# solar_rpof.net
KiCad netlist of a schematic drawn in EAGLE
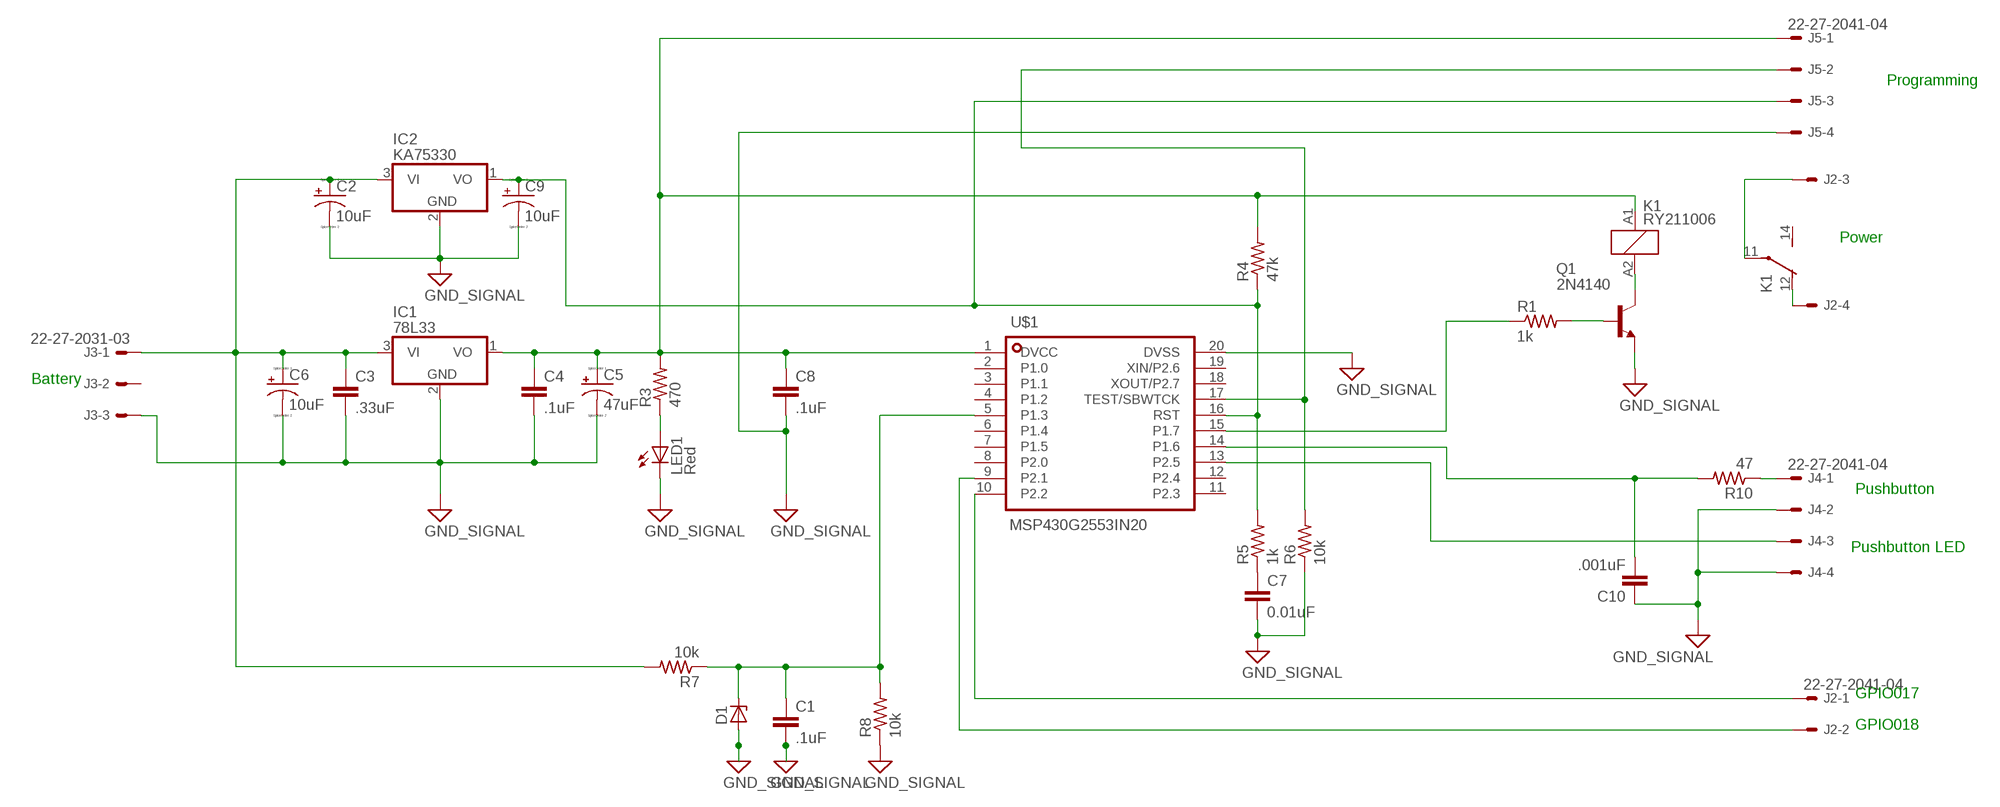
[diagram p0: schematic, sheet 1]

(export (version "E")
  (design (tool "Eeschema 10.0.6"))
  (components
    (comp (ref "C1")
      (value ".1uF")
      (footprint "eagle-import:C2.5-2")
      (libsource (lib "eagle-import") (part "C2.5/2"))
    )
    (comp (ref "C2")
      (value "10uF")
      (footprint "eagle-import:B45181A")
      (libsource (lib "eagle-import") (part "CPOL-USB45181A"))
    )
    (comp (ref "C3")
      (value ".33uF")
      (footprint "eagle-import:C2.5-2")
      (libsource (lib "eagle-import") (part "C2.5/2"))
    )
    (comp (ref "C4")
      (value ".1uF")
      (footprint "eagle-import:C2.5-2")
      (libsource (lib "eagle-import") (part "C2.5/2"))
    )
    (comp (ref "C5")
      (value "47uF")
      (footprint "eagle-import:B45181A")
      (libsource (lib "eagle-import") (part "CPOL-USB45181A"))
    )
    (comp (ref "C6")
      (value "10uF")
      (footprint "eagle-import:B45181A")
      (libsource (lib "eagle-import") (part "CPOL-USB45181A"))
    )
    (comp (ref "C7")
      (value "0.01uF")
      (footprint "eagle-import:C2.5-2")
      (libsource (lib "eagle-import") (part "C2.5/2"))
    )
    (comp (ref "C8")
      (value ".1uF")
      (footprint "eagle-import:C2.5-2")
      (libsource (lib "eagle-import") (part "C2.5/2"))
    )
    (comp (ref "C9")
      (value "10uF")
      (footprint "eagle-import:B45181A")
      (libsource (lib "eagle-import") (part "CPOL-USB45181A"))
    )
    (comp (ref "C10")
      (value ".001uF")
      (footprint "eagle-import:C2.5-2")
      (libsource (lib "eagle-import") (part "C2.5/2"))
    )
    (comp (ref "D1")
      (value "ZENER-DIODEDO34-7")
      (footprint "eagle-import:DO34Z7")
      (libsource (lib "eagle-import") (part "ZENER-DIODEDO34-7"))
    )
    (comp (ref "IC1")
      (value "78L33")
      (footprint "eagle-import:TO92")
      (libsource (lib "eagle-import") (part "78ZL05"))
    )
    (comp (ref "IC2")
      (value "KA75330")
      (footprint "eagle-import:TO92")
      (libsource (lib "eagle-import") (part "78ZL05"))
    )
    (comp (ref "J2")
      (value "22-27-2041-04")
      (footprint "eagle-import:6410-04")
      (libsource (lib "eagle-import") (part "22-?-0427-2041"))
    )
    (comp (ref "J3")
      (value "22-27-2031-03")
      (footprint "eagle-import:6410-03")
      (libsource (lib "eagle-import") (part "22-?-0327-2031"))
    )
    (comp (ref "J4")
      (value "22-27-2041-04")
      (footprint "eagle-import:6410-04")
      (libsource (lib "eagle-import") (part "22-?-0427-2041"))
    )
    (comp (ref "J5")
      (value "22-27-2041-04")
      (footprint "eagle-import:6410-04")
      (libsource (lib "eagle-import") (part "22-?-0427-2041"))
    )
    (comp (ref "K1")
      (value "RY211006")
      (footprint "eagle-import:RY-II")
      (fields (field (name "MF") "TYCO ELECTRONICS") (field (name "MPN") "4-1393224-3"))
      (libsource (lib "eagle-import") (part "RY?121006"))
    )
    (comp (ref "LED1")
      (value "Red")
      (footprint "eagle-import:LED3MM")
      (libsource (lib "eagle-import") (part "LED3MM"))
    )
    (comp (ref "Q1")
      (value "2N4140")
      (footprint "eagle-import:TO18")
      (libsource (lib "eagle-import") (part "2N4104"))
    )
    (comp (ref "R1")
      (value "1k")
      (footprint "eagle-import:0204_7")
      (libsource (lib "eagle-import") (part "R-US_0204/7"))
    )
    (comp (ref "R3")
      (value "470")
      (footprint "eagle-import:0204_7")
      (libsource (lib "eagle-import") (part "R-US_0204/7"))
    )
    (comp (ref "R4")
      (value "47k")
      (footprint "eagle-import:0204_7")
      (libsource (lib "eagle-import") (part "R-US_0204/7"))
    )
    (comp (ref "R5")
      (value "1k")
      (footprint "eagle-import:0204_7")
      (libsource (lib "eagle-import") (part "R-US_0204/7"))
    )
    (comp (ref "R6")
      (value "10k")
      (footprint "eagle-import:0204_7")
      (libsource (lib "eagle-import") (part "R-US_0204/7"))
    )
    (comp (ref "R7")
      (value "10k")
      (footprint "eagle-import:0204_7")
      (libsource (lib "eagle-import") (part "R-US_0204/7"))
    )
    (comp (ref "R8")
      (value "10k")
      (footprint "eagle-import:0204_7")
      (libsource (lib "eagle-import") (part "R-US_0204/7"))
    )
    (comp (ref "R10")
      (value "47")
      (footprint "eagle-import:0204_7")
      (libsource (lib "eagle-import") (part "R-US_0204/7"))
    )
    (comp (ref "U$1")
      (value "MSP430G2553IN20")
      (footprint "eagle-import:DIP20")
      (libsource (lib "eagle-import") (part "MSP430G2553IN20"))
    )
  )
  (nets
    (net (code "1") (name "GND_SIGNAL") (class "Default")
      (node (ref "C1") (pin "2") (pinfunction "2_2") (pintype "passive"))
      (node (ref "C10") (pin "1") (pinfunction "1_1") (pintype "passive"))
      (node (ref "C2") (pin "-") (pinfunction "-_-") (pintype "passive"))
      (node (ref "C3") (pin "2") (pinfunction "2_2") (pintype "passive"))
      (node (ref "C4") (pin "2") (pinfunction "2_2") (pintype "passive"))
      (node (ref "C5") (pin "-") (pinfunction "-_-") (pintype "passive"))
      (node (ref "C6") (pin "-") (pinfunction "-_-") (pintype "passive"))
      (node (ref "C7") (pin "2") (pinfunction "2_2") (pintype "passive"))
      (node (ref "C8") (pin "2") (pinfunction "2_2") (pintype "passive"))
      (node (ref "C9") (pin "-") (pinfunction "-_-") (pintype "passive"))
      (node (ref "D1") (pin "A") (pinfunction "A_A") (pintype "passive"))
      (node (ref "IC1") (pin "2") (pinfunction "GND_2") (pintype "passive"))
      (node (ref "IC2") (pin "2") (pinfunction "GND_2") (pintype "passive"))
      (node (ref "J3") (pin "3") (pinfunction "S_3") (pintype "passive"))
      (node (ref "J4") (pin "2") (pinfunction "S_2") (pintype "passive"))
      (node (ref "J4") (pin "4") (pinfunction "S_4") (pintype "passive"))
      (node (ref "J5") (pin "4") (pinfunction "S_4") (pintype "passive"))
      (node (ref "LED1") (pin "K") (pinfunction "C_K") (pintype "passive"))
      (node (ref "Q1") (pin "1") (pinfunction "E_1") (pintype "passive"))
      (node (ref "R6") (pin "1") (pinfunction "1_1") (pintype "passive"))
      (node (ref "R8") (pin "1") (pinfunction "1_1") (pintype "passive"))
      (node (ref "U$1") (pin "20") (pinfunction "DVSS_20") (pintype "power_in"))
    )
    (net (code "2") (name "Net-(C7-Pad1)") (class "Default")
      (node (ref "C7") (pin "1") (pinfunction "1_1") (pintype "passive"))
      (node (ref "R5") (pin "1") (pinfunction "1_1") (pintype "passive"))
    )
    (net (code "3") (name "Net-(IC1-VI)") (class "Default")
      (node (ref "C2") (pin "+") (pinfunction "+_+") (pintype "passive"))
      (node (ref "C3") (pin "1") (pinfunction "1_1") (pintype "passive"))
      (node (ref "C6") (pin "+") (pinfunction "+_+") (pintype "passive"))
      (node (ref "IC1") (pin "3") (pinfunction "VI_3") (pintype "input"))
      (node (ref "IC2") (pin "3") (pinfunction "VI_3") (pintype "input"))
      (node (ref "J3") (pin "1") (pinfunction "S_1") (pintype "passive"))
      (node (ref "R7") (pin "2") (pinfunction "2_2") (pintype "passive"))
    )
    (net (code "4") (name "Net-(IC1-VO)") (class "Default")
      (node (ref "C4") (pin "1") (pinfunction "1_1") (pintype "passive"))
      (node (ref "C5") (pin "+") (pinfunction "+_+") (pintype "passive"))
      (node (ref "C8") (pin "1") (pinfunction "1_1") (pintype "passive"))
      (node (ref "IC1") (pin "1") (pinfunction "VO_1") (pintype "passive"))
      (node (ref "J5") (pin "1") (pinfunction "S_1") (pintype "passive"))
      (node (ref "K1") (pin "A1") (pinfunction "1_A1") (pintype "passive"))
      (node (ref "R3") (pin "2") (pinfunction "2_2") (pintype "passive"))
      (node (ref "R4") (pin "2") (pinfunction "2_2") (pintype "passive"))
      (node (ref "U$1") (pin "1") (pinfunction "DVCC_1") (pintype "power_in"))
    )
    (net (code "5") (name "Net-(IC2-VO)") (class "Default")
      (node (ref "C9") (pin "+") (pinfunction "+_+") (pintype "passive"))
      (node (ref "IC2") (pin "1") (pinfunction "VO_1") (pintype "passive"))
      (node (ref "J5") (pin "3") (pinfunction "S_3") (pintype "passive"))
      (node (ref "R4") (pin "1") (pinfunction "1_1") (pintype "passive"))
      (node (ref "R5") (pin "2") (pinfunction "2_2") (pintype "passive"))
      (node (ref "U$1") (pin "16") (pinfunction "RST_16") (pintype "bidirectional"))
    )
    (net (code "6") (name "Net-(J2A-S)") (class "Default")
      (node (ref "J2") (pin "1") (pinfunction "S_1") (pintype "passive"))
      (node (ref "U$1") (pin "10") (pinfunction "P2.2_10") (pintype "bidirectional"))
    )
    (net (code "7") (name "Net-(J2B-S)") (class "Default")
      (node (ref "J2") (pin "2") (pinfunction "S_2") (pintype "passive"))
      (node (ref "U$1") (pin "9") (pinfunction "P2.1_9") (pintype "bidirectional"))
    )
    (net (code "8") (name "Net-(J2C-S)") (class "Default")
      (node (ref "J2") (pin "3") (pinfunction "S_3") (pintype "passive"))
      (node (ref "K1") (pin "11") (pinfunction "P_11") (pintype "passive"))
    )
    (net (code "9") (name "Net-(J2D-S)") (class "Default")
      (node (ref "J2") (pin "4") (pinfunction "S_4") (pintype "passive"))
      (node (ref "K1") (pin "12") (pinfunction "O_12") (pintype "passive"))
    )
    (net (code "10") (name "Net-(J4A-S)") (class "Default")
      (node (ref "J4") (pin "1") (pinfunction "S_1") (pintype "passive"))
      (node (ref "R10") (pin "1") (pinfunction "1_1") (pintype "passive"))
    )
    (net (code "11") (name "Net-(J4C-S)") (class "Default")
      (node (ref "J4") (pin "3") (pinfunction "S_3") (pintype "passive"))
      (node (ref "U$1") (pin "13") (pinfunction "P2.5_13") (pintype "bidirectional"))
    )
    (net (code "12") (name "Net-(J5B-S)") (class "Default")
      (node (ref "J5") (pin "2") (pinfunction "S_2") (pintype "passive"))
      (node (ref "R6") (pin "2") (pinfunction "2_2") (pintype "passive"))
      (node (ref "U$1") (pin "17") (pinfunction "TEST/SBWTCK_17") (pintype "bidirectional"))
    )
    (net (code "13") (name "Net-(K1A-2)") (class "Default")
      (node (ref "K1") (pin "A2") (pinfunction "2_A2") (pintype "passive"))
      (node (ref "Q1") (pin "3") (pinfunction "C_3") (pintype "passive"))
    )
    (net (code "14") (name "Net-(LED1-PadA)") (class "Default")
      (node (ref "LED1") (pin "A") (pinfunction "A_A") (pintype "passive"))
      (node (ref "R3") (pin "1") (pinfunction "1_1") (pintype "passive"))
    )
    (net (code "15") (name "Net-(Q1-B)") (class "Default")
      (node (ref "Q1") (pin "2") (pinfunction "B_2") (pintype "passive"))
      (node (ref "R1") (pin "2") (pinfunction "2_2") (pintype "passive"))
    )
    (net (code "16") (name "Net-(U$1-P1.3)") (class "Default")
      (node (ref "C1") (pin "1") (pinfunction "1_1") (pintype "passive"))
      (node (ref "D1") (pin "C") (pinfunction "C_C") (pintype "passive"))
      (node (ref "R7") (pin "1") (pinfunction "1_1") (pintype "passive"))
      (node (ref "R8") (pin "2") (pinfunction "2_2") (pintype "passive"))
      (node (ref "U$1") (pin "5") (pinfunction "P1.3_5") (pintype "bidirectional"))
    )
    (net (code "17") (name "Net-(U$1-P1.6)") (class "Default")
      (node (ref "C10") (pin "2") (pinfunction "2_2") (pintype "passive"))
      (node (ref "R10") (pin "2") (pinfunction "2_2") (pintype "passive"))
      (node (ref "U$1") (pin "14") (pinfunction "P1.6_14") (pintype "bidirectional"))
    )
    (net (code "18") (name "Net-(U$1-P1.7)") (class "Default")
      (node (ref "R1") (pin "1") (pinfunction "1_1") (pintype "passive"))
      (node (ref "U$1") (pin "15") (pinfunction "P1.7_15") (pintype "bidirectional"))
    )
    (net (code "19") (name "unconnected-(J3B-S-Pad2)") (class "Default")
      (node (ref "J3") (pin "2") (pinfunction "S_2") (pintype "passive"))
    )
    (net (code "20") (name "unconnected-(K1B-S-Pad14)") (class "Default")
      (node (ref "K1") (pin "14") (pinfunction "S_14") (pintype "passive"))
    )
    (net (code "21") (name "unconnected-(U$1-P1.0-Pad2)") (class "Default")
      (node (ref "U$1") (pin "2") (pinfunction "P1.0_2") (pintype "bidirectional"))
    )
    (net (code "22") (name "unconnected-(U$1-P1.1-Pad3)") (class "Default")
      (node (ref "U$1") (pin "3") (pinfunction "P1.1_3") (pintype "bidirectional"))
    )
    (net (code "23") (name "unconnected-(U$1-P1.2-Pad4)") (class "Default")
      (node (ref "U$1") (pin "4") (pinfunction "P1.2_4") (pintype "bidirectional"))
    )
    (net (code "24") (name "unconnected-(U$1-P1.4-Pad6)") (class "Default")
      (node (ref "U$1") (pin "6") (pinfunction "P1.4_6") (pintype "bidirectional"))
    )
    (net (code "25") (name "unconnected-(U$1-P1.5-Pad7)") (class "Default")
      (node (ref "U$1") (pin "7") (pinfunction "P1.5_7") (pintype "bidirectional"))
    )
    (net (code "26") (name "unconnected-(U$1-P2.0-Pad8)") (class "Default")
      (node (ref "U$1") (pin "8") (pinfunction "P2.0_8") (pintype "bidirectional"))
    )
    (net (code "27") (name "unconnected-(U$1-P2.3-Pad11)") (class "Default")
      (node (ref "U$1") (pin "11") (pinfunction "P2.3_11") (pintype "bidirectional"))
    )
    (net (code "28") (name "unconnected-(U$1-P2.4-Pad12)") (class "Default")
      (node (ref "U$1") (pin "12") (pinfunction "P2.4_12") (pintype "bidirectional"))
    )
    (net (code "29") (name "unconnected-(U$1-XIN{slash}P2.6-Pad19)") (class "Default")
      (node (ref "U$1") (pin "19") (pinfunction "XIN/P2.6_19") (pintype "bidirectional"))
    )
    (net (code "30") (name "unconnected-(U$1-XOUT{slash}P2.7-Pad18)") (class "Default")
      (node (ref "U$1") (pin "18") (pinfunction "XOUT/P2.7_18") (pintype "bidirectional"))
    )
  )
)
